# v1-cockroach.net
KiCad netlist of a schematic drawn in EAGLE
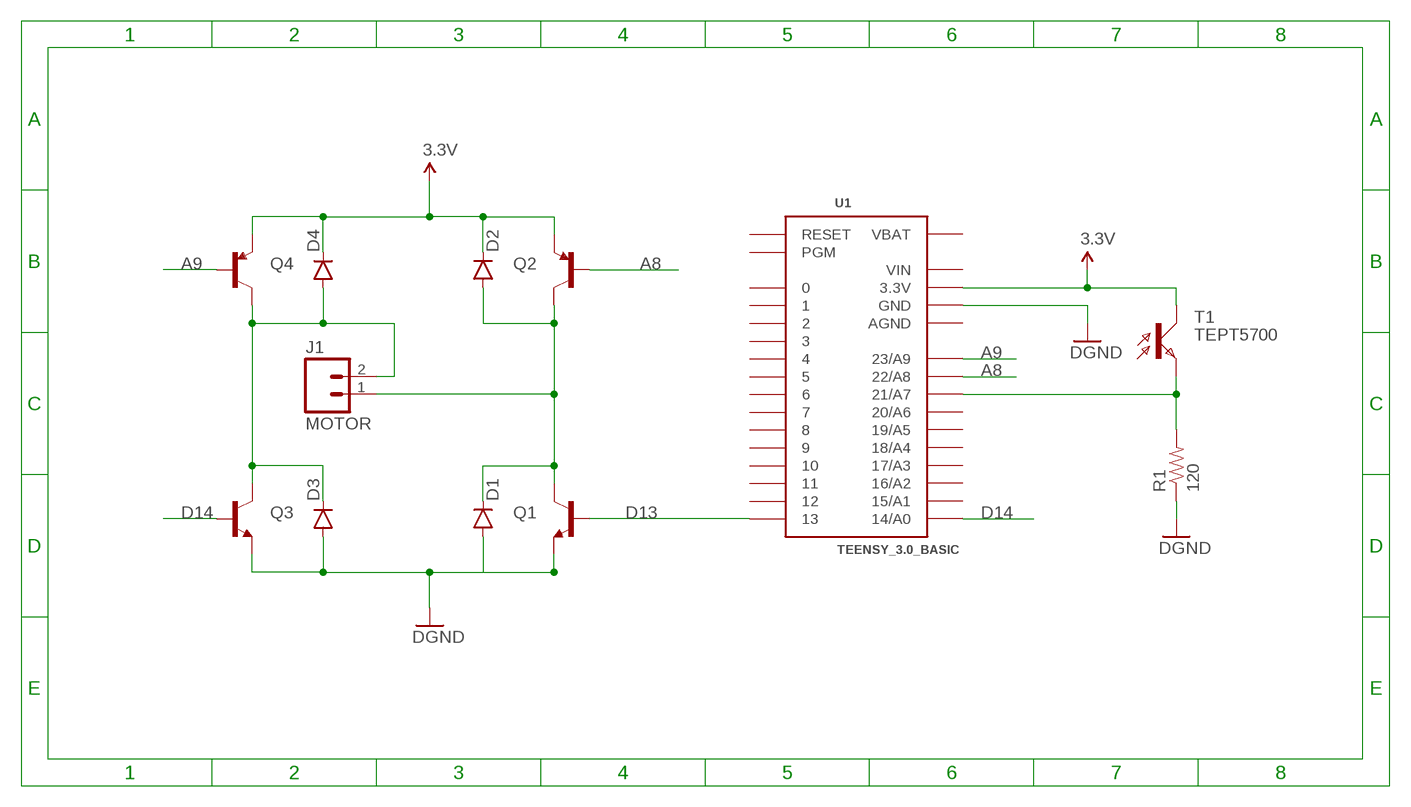
[diagram p0: schematic, sheet 1]

(export (version "E")
  (design (tool "Eeschema 10.0.6"))
  (components
    (comp (ref "D1")
      (value "DIODE")
      (footprint "eagle-import:DIODE-1N4001-KIT")
      (libsource (lib "eagle-import") (part "DIODE"))
    )
    (comp (ref "D2")
      (value "DIODE")
      (footprint "eagle-import:DIODE-1N4001-KIT")
      (libsource (lib "eagle-import") (part "DIODE"))
    )
    (comp (ref "D3")
      (value "DIODE")
      (footprint "eagle-import:DIODE-1N4001-KIT")
      (libsource (lib "eagle-import") (part "DIODE"))
    )
    (comp (ref "D4")
      (value "DIODE")
      (footprint "eagle-import:DIODE-1N4001-KIT")
      (libsource (lib "eagle-import") (part "DIODE"))
    )
    (comp (ref "J1")
      (value "MOTOR")
      (footprint "eagle-import:1X02_LOCK")
      (libsource (lib "eagle-import") (part "M02LOCK"))
    )
    (comp (ref "Q1")
      (value "TRANSISTOR_NPNBC547")
      (footprint "eagle-import:TO-92-AMMO")
      (libsource (lib "eagle-import") (part "TRANSISTOR_NPNBC547"))
    )
    (comp (ref "Q2")
      (value "TRANSISTOR_PNPTO92")
      (footprint "eagle-import:TO-92")
      (libsource (lib "eagle-import") (part "TRANSISTOR_PNPTO92"))
    )
    (comp (ref "Q3")
      (value "TRANSISTOR_NPNBC547")
      (footprint "eagle-import:TO-92-AMMO")
      (libsource (lib "eagle-import") (part "TRANSISTOR_NPNBC547"))
    )
    (comp (ref "Q4")
      (value "TRANSISTOR_PNPTO92")
      (footprint "eagle-import:TO-92")
      (libsource (lib "eagle-import") (part "TRANSISTOR_PNPTO92"))
    )
    (comp (ref "R1")
      (value "120")
      (footprint "eagle-import:AXIAL-0.3EZ")
      (libsource (lib "eagle-import") (part "RESISTOREZ"))
    )
    (comp (ref "T1")
      (value "TEPT5700")
      (footprint "eagle-import:BPX81")
      (libsource (lib "eagle-import") (part "BPX81"))
    )
    (comp (ref "U1")
      (value "TEENSY_3.0_BASIC")
      (footprint "eagle-import:TEENSY_3.0_BASIC")
      (libsource (lib "eagle-import") (part "TEENSY_3.0_BASIC"))
    )
  )
  (nets
    (net (code "1") (name "/A8") (class "Default")
      (node (ref "Q2") (pin "2") (pinfunction "B_2") (pintype "passive"))
      (node (ref "U1") (pin "22/A8") (pinfunction "22/A8_22/A8") (pintype "bidirectional"))
    )
    (net (code "2") (name "/A9") (class "Default")
      (node (ref "Q4") (pin "2") (pinfunction "B_2") (pintype "passive"))
      (node (ref "U1") (pin "23/A9") (pinfunction "23/A9_23/A9") (pintype "bidirectional"))
    )
    (net (code "3") (name "/AGND") (class "Default")
      (node (ref "U1") (pin "AGND") (pinfunction "AGND_AGND") (pintype "power_in"))
    )
    (net (code "4") (name "/D13") (class "Default")
      (node (ref "Q1") (pin "2") (pinfunction "B_2") (pintype "passive"))
      (node (ref "U1") (pin "13") (pinfunction "13_13") (pintype "bidirectional"))
    )
    (net (code "5") (name "/D14") (class "Default")
      (node (ref "Q3") (pin "2") (pinfunction "B_2") (pintype "passive"))
      (node (ref "U1") (pin "14/A0") (pinfunction "14/A0_14/A0") (pintype "bidirectional"))
    )
    (net (code "6") (name "/VBAT") (class "Default")
      (node (ref "U1") (pin "VBAT") (pinfunction "VBAT_VBAT") (pintype "power_in"))
    )
    (net (code "7") (name "/VIN") (class "Default")
      (node (ref "U1") (pin "VIN") (pinfunction "VIN_VIN") (pintype "power_in"))
    )
    (net (code "8") (name "3.3V") (class "Default")
      (node (ref "D2") (pin "C") (pinfunction "C_C") (pintype "passive"))
      (node (ref "D4") (pin "C") (pinfunction "C_C") (pintype "passive"))
      (node (ref "Q2") (pin "1") (pinfunction "E_1") (pintype "passive"))
      (node (ref "Q4") (pin "1") (pinfunction "E_1") (pintype "passive"))
      (node (ref "T1") (pin "C") (pinfunction "C_C") (pintype "passive"))
      (node (ref "U1") (pin "3.3V") (pinfunction "3.3V_3.3V") (pintype "power_in"))
      (node (ref "U1") (pin "3.3V1") (pinfunction "3.3V_3.3V1") (pintype "power_in"))
    )
    (net (code "9") (name "DGND") (class "Default")
      (node (ref "D1") (pin "A") (pinfunction "A_A") (pintype "passive"))
      (node (ref "D3") (pin "A") (pinfunction "A_A") (pintype "passive"))
      (node (ref "Q1") (pin "3") (pinfunction "E_3") (pintype "passive"))
      (node (ref "Q3") (pin "3") (pinfunction "E_3") (pintype "passive"))
      (node (ref "R1") (pin "P$1") (pinfunction "1_P$1") (pintype "passive"))
      (node (ref "U1") (pin "GND") (pinfunction "GND_GND") (pintype "power_in"))
      (node (ref "U1") (pin "GND1") (pinfunction "GND_GND1") (pintype "power_in"))
    )
    (net (code "10") (name "Net-(Q1-C)") (class "Default")
      (node (ref "D1") (pin "C") (pinfunction "C_C") (pintype "passive"))
      (node (ref "D2") (pin "A") (pinfunction "A_A") (pintype "passive"))
      (node (ref "J1") (pin "1") (pinfunction "1_1") (pintype "passive"))
      (node (ref "Q1") (pin "1") (pinfunction "C_1") (pintype "passive"))
      (node (ref "Q2") (pin "3") (pinfunction "C_3") (pintype "passive"))
    )
    (net (code "11") (name "Net-(Q3-C)") (class "Default")
      (node (ref "D3") (pin "C") (pinfunction "C_C") (pintype "passive"))
      (node (ref "D4") (pin "A") (pinfunction "A_A") (pintype "passive"))
      (node (ref "J1") (pin "2") (pinfunction "2_2") (pintype "passive"))
      (node (ref "Q3") (pin "1") (pinfunction "C_1") (pintype "passive"))
      (node (ref "Q4") (pin "3") (pinfunction "C_3") (pintype "passive"))
    )
    (net (code "12") (name "Net-(R1-2)") (class "Default")
      (node (ref "R1") (pin "P$2") (pinfunction "2_P$2") (pintype "passive"))
      (node (ref "T1") (pin "E") (pinfunction "E_E") (pintype "passive"))
      (node (ref "U1") (pin "21/A7") (pinfunction "21/A7_21/A7") (pintype "bidirectional"))
    )
    (net (code "13") (name "unconnected-(U1-Pad0)") (class "Default")
      (node (ref "U1") (pin "0") (pinfunction "0_0") (pintype "bidirectional"))
    )
    (net (code "14") (name "unconnected-(U1-Pad1)") (class "Default")
      (node (ref "U1") (pin "1") (pinfunction "1_1") (pintype "bidirectional"))
    )
    (net (code "15") (name "unconnected-(U1-Pad2)") (class "Default")
      (node (ref "U1") (pin "2") (pinfunction "2_2") (pintype "bidirectional"))
    )
    (net (code "16") (name "unconnected-(U1-Pad3)") (class "Default")
      (node (ref "U1") (pin "3") (pinfunction "3_3") (pintype "bidirectional"))
    )
    (net (code "17") (name "unconnected-(U1-Pad4)") (class "Default")
      (node (ref "U1") (pin "4") (pinfunction "4_4") (pintype "bidirectional"))
    )
    (net (code "18") (name "unconnected-(U1-Pad5)") (class "Default")
      (node (ref "U1") (pin "5") (pinfunction "5_5") (pintype "bidirectional"))
    )
    (net (code "19") (name "unconnected-(U1-Pad6)") (class "Default")
      (node (ref "U1") (pin "6") (pinfunction "6_6") (pintype "bidirectional"))
    )
    (net (code "20") (name "unconnected-(U1-Pad7)") (class "Default")
      (node (ref "U1") (pin "7") (pinfunction "7_7") (pintype "bidirectional"))
    )
    (net (code "21") (name "unconnected-(U1-Pad8)") (class "Default")
      (node (ref "U1") (pin "8") (pinfunction "8_8") (pintype "bidirectional"))
    )
    (net (code "22") (name "unconnected-(U1-Pad9)") (class "Default")
      (node (ref "U1") (pin "9") (pinfunction "9_9") (pintype "bidirectional"))
    )
    (net (code "23") (name "unconnected-(U1-Pad10)") (class "Default")
      (node (ref "U1") (pin "10") (pinfunction "10_10") (pintype "bidirectional"))
    )
    (net (code "24") (name "unconnected-(U1-Pad11)") (class "Default")
      (node (ref "U1") (pin "11") (pinfunction "11_11") (pintype "bidirectional"))
    )
    (net (code "25") (name "unconnected-(U1-Pad12)") (class "Default")
      (node (ref "U1") (pin "12") (pinfunction "12_12") (pintype "bidirectional"))
    )
    (net (code "26") (name "unconnected-(U1-Pad15{slash}A1)") (class "Default")
      (node (ref "U1") (pin "15/A1") (pinfunction "15/A1_15/A1") (pintype "bidirectional"))
    )
    (net (code "27") (name "unconnected-(U1-Pad16{slash}A2)") (class "Default")
      (node (ref "U1") (pin "16/A2") (pinfunction "16/A2_16/A2") (pintype "bidirectional"))
    )
    (net (code "28") (name "unconnected-(U1-Pad17{slash}A3)") (class "Default")
      (node (ref "U1") (pin "17/A3") (pinfunction "17/A3_17/A3") (pintype "bidirectional"))
    )
    (net (code "29") (name "unconnected-(U1-Pad18{slash}A4)") (class "Default")
      (node (ref "U1") (pin "18/A4") (pinfunction "18/A4_18/A4") (pintype "bidirectional"))
    )
    (net (code "30") (name "unconnected-(U1-Pad19{slash}A5)") (class "Default")
      (node (ref "U1") (pin "19/A5") (pinfunction "19/A5_19/A5") (pintype "bidirectional"))
    )
    (net (code "31") (name "unconnected-(U1-Pad20{slash}A6)") (class "Default")
      (node (ref "U1") (pin "20/A6") (pinfunction "20/A6_20/A6") (pintype "bidirectional"))
    )
    (net (code "32") (name "unconnected-(U1-PadPGM)") (class "Default")
      (node (ref "U1") (pin "PGM") (pinfunction "PGM_PGM") (pintype "bidirectional"))
    )
    (net (code "33") (name "unconnected-(U1-PadRESET)") (class "Default")
      (node (ref "U1") (pin "RESET") (pinfunction "RESET_RESET") (pintype "bidirectional"))
    )
  )
)
